# 2_mcu.net
KiCad netlist of a schematic drawn in Altium Designer
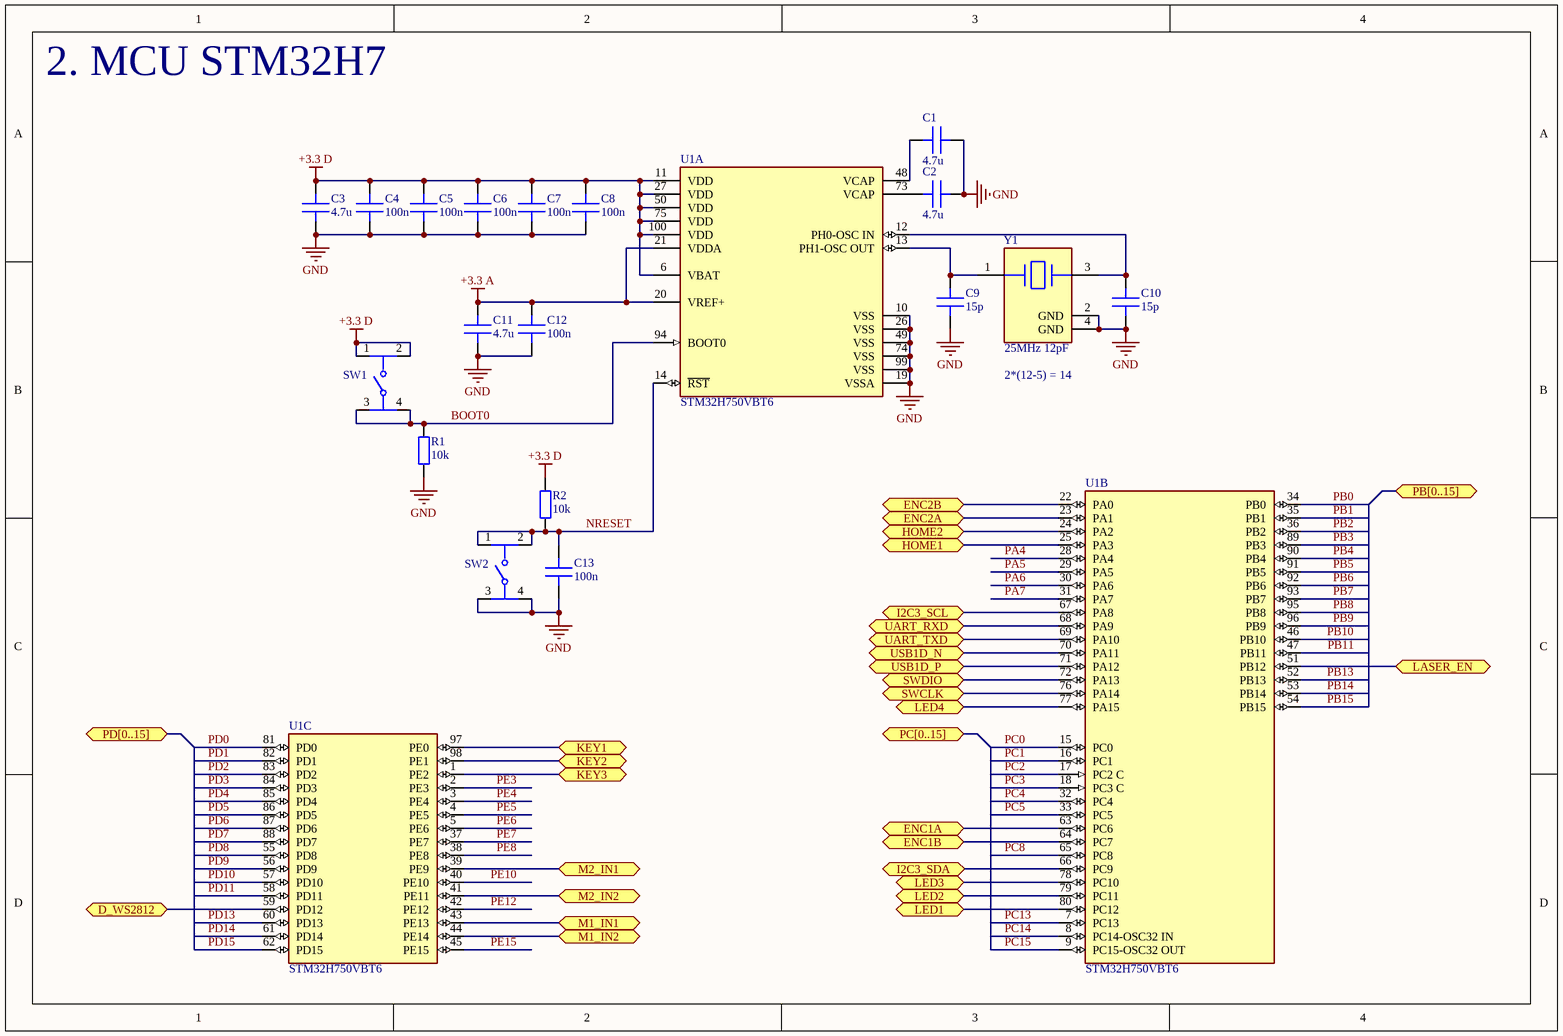
[diagram p0: 2_mcu.SchDoc]

(export (version "E")
  (design (tool "Eeschema 10.0.6"))
  (components
    (comp (ref "C1")
      (value "4.7u")
      (footprint "IPC C C0603 NO SILK")
      (libsource (lib "JLCPCB Library") (part "Generic CAP 0603"))
    )
    (comp (ref "C2")
      (value "4.7u")
      (footprint "IPC C C0603 NO SILK")
      (libsource (lib "JLCPCB Library") (part "Generic CAP 0603"))
    )
    (comp (ref "C3")
      (value "4.7u")
      (footprint "IPC C C0603 NO SILK")
      (libsource (lib "JLCPCB Library") (part "Generic CAP 0603"))
    )
    (comp (ref "C4")
      (value "100n")
      (footprint "IPC C C0402 NO SILK")
      (libsource (lib "JLCPCB Library") (part "Generic CAP 0402"))
    )
    (comp (ref "C5")
      (value "100n")
      (footprint "IPC C C0402 NO SILK")
      (libsource (lib "JLCPCB Library") (part "Generic CAP 0402"))
    )
    (comp (ref "C6")
      (value "100n")
      (footprint "IPC C C0402 NO SILK")
      (libsource (lib "JLCPCB Library") (part "Generic CAP 0402"))
    )
    (comp (ref "C7")
      (value "100n")
      (footprint "IPC C C0402 NO SILK")
      (libsource (lib "JLCPCB Library") (part "Generic CAP 0402"))
    )
    (comp (ref "C8")
      (value "100n")
      (footprint "IPC C C0402 NO SILK")
      (libsource (lib "JLCPCB Library") (part "Generic CAP 0402"))
    )
    (comp (ref "C9")
      (value "15p")
      (footprint "IPC C C0402 NO SILK")
      (libsource (lib "JLCPCB Library") (part "Generic CAP 0402"))
    )
    (comp (ref "C10")
      (value "15p")
      (footprint "IPC C C0402 NO SILK")
      (libsource (lib "JLCPCB Library") (part "Generic CAP 0402"))
    )
    (comp (ref "C11")
      (value "4.7u")
      (footprint "IPC C C0603 NO SILK")
      (libsource (lib "JLCPCB Library") (part "Generic CAP 0603"))
    )
    (comp (ref "C12")
      (value "100n")
      (footprint "IPC C C0402 NO SILK")
      (libsource (lib "JLCPCB Library") (part "Generic CAP 0402"))
    )
    (comp (ref "C13")
      (value "100n")
      (footprint "IPC C C0402 NO SILK")
      (libsource (lib "JLCPCB Library") (part "Generic CAP 0402"))
    )
    (comp (ref "R1")
      (value "10k")
      (footprint "IPC C R0402 NO SILK")
      (libsource (lib "JLCPCB Library") (part "Generic RES 0402"))
    )
    (comp (ref "R2")
      (value "10k")
      (footprint "IPC C R0402 NO SILK")
      (libsource (lib "JLCPCB Library") (part "Generic RES 0402"))
    )
    (comp (ref "SW1")
      (value "PTS810SJM250SMTRLFS")
      (footprint "FP-PTS810SJM250SMTRLFS-MFG")
      (description "SWITCH TACTILE SPST-NO 0.05A 16V")
      (libsource (lib "Altium Content Vault") (part "1adf0dd01260c80cf25a44bfd6b99ba"))
    )
    (comp (ref "SW2")
      (value "PTS810SJM250SMTRLFS")
      (footprint "FP-PTS810SJM250SMTRLFS-MFG")
      (description "SWITCH TACTILE SPST-NO 0.05A 16V")
      (libsource (lib "Altium Content Vault") (part "1adf0dd01260c80cf25a44bfd6b99ba"))
    )
    (comp (ref "U1")
      (value "STM32H750VBT6")
      (footprint "FP-LQFP100-1L-MFG")
      (description "IC MCU 32BIT 128KB FLASH 100LQFP")
      (fields
        (field (name "OCTOPART") "https://octopart.com/stm32h750vbt6-stmicroelectronics-94048547")
        (field (name "MANUFACTURER") "STMicroelectronics")
      )
      (libsource (lib "Altium Content Vault") (part "aca449acb2b80670ba40d015d68dc7a"))
    )
    (comp (ref "Y1")
      (value "ABM8G-25.000MHZ-B4Y-T")
      (footprint "FP-ABM8G-MFG")
      (description "Crystal 25MHz ±30ppm (Tol) ±30ppm (Stability) 10pF FUND 60Ω 4-Pin SMD T/R")
      (fields (field (name "TOLERANCE") "30ppm"))
      (libsource (lib "Altium Content Vault") (part "48e526d86b7f2615d98721063c72f49"))
    )
  )
  (nets
    (net (code "9") (name "+3.3 A") (class "Default")
      (node (ref "C11") (pin "2") (pinfunction "2_2") (pintype "passive"))
      (node (ref "C12") (pin "2") (pinfunction "2_2") (pintype "passive"))
      (node (ref "U1") (pin "20") (pinfunction "VREF+_20") (pintype "power_in"))
      (node (ref "U1") (pin "21") (pinfunction "VDDA_21") (pintype "power_in"))
    )
    (net (code "10") (name "+3.3 D") (class "Default")
      (node (ref "C3") (pin "2") (pinfunction "2_2") (pintype "passive"))
      (node (ref "C4") (pin "2") (pinfunction "2_2") (pintype "passive"))
      (node (ref "C5") (pin "2") (pinfunction "2_2") (pintype "passive"))
      (node (ref "C6") (pin "2") (pinfunction "2_2") (pintype "passive"))
      (node (ref "C7") (pin "2") (pinfunction "2_2") (pintype "passive"))
      (node (ref "C8") (pin "2") (pinfunction "2_2") (pintype "passive"))
      (node (ref "R2") (pin "1") (pinfunction "1_1") (pintype "passive"))
      (node (ref "SW1") (pin "1") (pinfunction "1_1") (pintype "passive"))
      (node (ref "SW1") (pin "2") (pinfunction "2_2") (pintype "passive"))
      (node (ref "U1") (pin "100") (pinfunction "VDD_100") (pintype "power_in"))
      (node (ref "U1") (pin "11") (pinfunction "VDD_11") (pintype "power_in"))
      (node (ref "U1") (pin "27") (pinfunction "VDD_27") (pintype "power_in"))
      (node (ref "U1") (pin "50") (pinfunction "VDD_50") (pintype "power_in"))
      (node (ref "U1") (pin "6") (pinfunction "VBAT_6") (pintype "power_in"))
      (node (ref "U1") (pin "75") (pinfunction "VDD_75") (pintype "power_in"))
    )
    (net (code "11") (name "/BOOT0") (class "Default")
      (node (ref "R1") (pin "1") (pinfunction "1_1") (pintype "passive"))
      (node (ref "SW1") (pin "3") (pinfunction "3_3") (pintype "passive"))
      (node (ref "SW1") (pin "4") (pinfunction "4_4") (pintype "passive"))
      (node (ref "U1") (pin "94") (pinfunction "BOOT0_94") (pintype "input"))
    )
    (net (code "12") (name "/D_WS2812") (class "Default")
      (node (ref "U1") (pin "59") (pinfunction "PD12_59") (pintype "bidirectional"))
    )
    (net (code "13") (name "/ENC1A") (class "Default")
      (node (ref "U1") (pin "63") (pinfunction "PC6_63") (pintype "bidirectional"))
    )
    (net (code "14") (name "/ENC1B") (class "Default")
      (node (ref "U1") (pin "64") (pinfunction "PC7_64") (pintype "bidirectional"))
    )
    (net (code "15") (name "/ENC2A") (class "Default")
      (node (ref "U1") (pin "23") (pinfunction "PA1_23") (pintype "bidirectional"))
    )
    (net (code "16") (name "/ENC2B") (class "Default")
      (node (ref "U1") (pin "22") (pinfunction "PA0_22") (pintype "bidirectional"))
    )
    (net (code "17") (name "/HOME1") (class "Default")
      (node (ref "U1") (pin "25") (pinfunction "PA3_25") (pintype "bidirectional"))
    )
    (net (code "18") (name "/HOME2") (class "Default")
      (node (ref "U1") (pin "24") (pinfunction "PA2_24") (pintype "bidirectional"))
    )
    (net (code "19") (name "/I2C3_SCL") (class "Default")
      (node (ref "U1") (pin "67") (pinfunction "PA8_67") (pintype "bidirectional"))
    )
    (net (code "20") (name "/I2C3_SDA") (class "Default")
      (node (ref "U1") (pin "66") (pinfunction "PC9_66") (pintype "bidirectional"))
    )
    (net (code "21") (name "/KEY1") (class "Default")
      (node (ref "U1") (pin "97") (pinfunction "PE0_97") (pintype "bidirectional"))
    )
    (net (code "22") (name "/KEY2") (class "Default")
      (node (ref "U1") (pin "98") (pinfunction "PE1_98") (pintype "bidirectional"))
    )
    (net (code "23") (name "/KEY3") (class "Default")
      (node (ref "U1") (pin "1") (pinfunction "PE2_1") (pintype "bidirectional"))
    )
    (net (code "24") (name "/LASER_EN") (class "Default")
      (node (ref "U1") (pin "51") (pinfunction "PB12_51") (pintype "bidirectional"))
    )
    (net (code "25") (name "/LED1") (class "Default")
      (node (ref "U1") (pin "80") (pinfunction "PC12_80") (pintype "bidirectional"))
    )
    (net (code "26") (name "/LED2") (class "Default")
      (node (ref "U1") (pin "79") (pinfunction "PC11_79") (pintype "bidirectional"))
    )
    (net (code "27") (name "/LED3") (class "Default")
      (node (ref "U1") (pin "78") (pinfunction "PC10_78") (pintype "bidirectional"))
    )
    (net (code "28") (name "/LED4") (class "Default")
      (node (ref "U1") (pin "77") (pinfunction "PA15_77") (pintype "bidirectional"))
    )
    (net (code "29") (name "/M1_IN1") (class "Default")
      (node (ref "U1") (pin "43") (pinfunction "PE13_43") (pintype "bidirectional"))
    )
    (net (code "30") (name "/M1_IN2") (class "Default")
      (node (ref "U1") (pin "44") (pinfunction "PE14_44") (pintype "bidirectional"))
    )
    (net (code "31") (name "/M2_IN1") (class "Default")
      (node (ref "U1") (pin "39") (pinfunction "PE9_39") (pintype "bidirectional"))
    )
    (net (code "32") (name "/M2_IN2") (class "Default")
      (node (ref "U1") (pin "41") (pinfunction "PE11_41") (pintype "bidirectional"))
    )
    (net (code "33") (name "/NRESET") (class "Default")
      (node (ref "C13") (pin "2") (pinfunction "2_2") (pintype "passive"))
      (node (ref "R2") (pin "2") (pinfunction "2_2") (pintype "passive"))
      (node (ref "SW2") (pin "1") (pinfunction "1_1") (pintype "passive"))
      (node (ref "SW2") (pin "2") (pinfunction "2_2") (pintype "passive"))
      (node (ref "U1") (pin "14") (pinfunction "~{RST}_14") (pintype "bidirectional"))
    )
    (net (code "34") (name "/PA4") (class "Default")
      (node (ref "U1") (pin "28") (pinfunction "PA4_28") (pintype "bidirectional"))
    )
    (net (code "35") (name "/PA5") (class "Default")
      (node (ref "U1") (pin "29") (pinfunction "PA5_29") (pintype "bidirectional"))
    )
    (net (code "36") (name "/PA6") (class "Default")
      (node (ref "U1") (pin "30") (pinfunction "PA6_30") (pintype "bidirectional"))
    )
    (net (code "37") (name "/PA7") (class "Default")
      (node (ref "U1") (pin "31") (pinfunction "PA7_31") (pintype "bidirectional"))
    )
    (net (code "38") (name "/PB0") (class "Default")
      (node (ref "U1") (pin "34") (pinfunction "PB0_34") (pintype "bidirectional"))
    )
    (net (code "39") (name "/PB1") (class "Default")
      (node (ref "U1") (pin "35") (pinfunction "PB1_35") (pintype "bidirectional"))
    )
    (net (code "40") (name "/PB2") (class "Default")
      (node (ref "U1") (pin "36") (pinfunction "PB2_36") (pintype "bidirectional"))
    )
    (net (code "41") (name "/PB3") (class "Default")
      (node (ref "U1") (pin "89") (pinfunction "PB3_89") (pintype "bidirectional"))
    )
    (net (code "42") (name "/PB4") (class "Default")
      (node (ref "U1") (pin "90") (pinfunction "PB4_90") (pintype "bidirectional"))
    )
    (net (code "43") (name "/PB5") (class "Default")
      (node (ref "U1") (pin "91") (pinfunction "PB5_91") (pintype "bidirectional"))
    )
    (net (code "44") (name "/PB6") (class "Default")
      (node (ref "U1") (pin "92") (pinfunction "PB6_92") (pintype "bidirectional"))
    )
    (net (code "45") (name "/PB7") (class "Default")
      (node (ref "U1") (pin "93") (pinfunction "PB7_93") (pintype "bidirectional"))
    )
    (net (code "46") (name "/PB8") (class "Default")
      (node (ref "U1") (pin "95") (pinfunction "PB8_95") (pintype "bidirectional"))
    )
    (net (code "47") (name "/PB9") (class "Default")
      (node (ref "U1") (pin "96") (pinfunction "PB9_96") (pintype "bidirectional"))
    )
    (net (code "48") (name "/PB10") (class "Default")
      (node (ref "U1") (pin "46") (pinfunction "PB10_46") (pintype "bidirectional"))
    )
    (net (code "49") (name "/PB11") (class "Default")
      (node (ref "U1") (pin "47") (pinfunction "PB11_47") (pintype "bidirectional"))
    )
    (net (code "50") (name "/PB13") (class "Default")
      (node (ref "U1") (pin "52") (pinfunction "PB13_52") (pintype "bidirectional"))
    )
    (net (code "51") (name "/PB14") (class "Default")
      (node (ref "U1") (pin "53") (pinfunction "PB14_53") (pintype "bidirectional"))
    )
    (net (code "52") (name "/PB15") (class "Default")
      (node (ref "U1") (pin "54") (pinfunction "PB15_54") (pintype "bidirectional"))
    )
    (net (code "54") (name "/PC0") (class "Default")
      (node (ref "U1") (pin "15") (pinfunction "PC0_15") (pintype "bidirectional"))
    )
    (net (code "55") (name "/PC1") (class "Default")
      (node (ref "U1") (pin "16") (pinfunction "PC1_16") (pintype "bidirectional"))
    )
    (net (code "56") (name "/PC2") (class "Default")
      (node (ref "U1") (pin "17") (pinfunction "PC2_C_17") (pintype "input"))
    )
    (net (code "57") (name "/PC3") (class "Default")
      (node (ref "U1") (pin "18") (pinfunction "PC3_C_18") (pintype "input"))
    )
    (net (code "58") (name "/PC4") (class "Default")
      (node (ref "U1") (pin "32") (pinfunction "PC4_32") (pintype "bidirectional"))
    )
    (net (code "59") (name "/PC5") (class "Default")
      (node (ref "U1") (pin "33") (pinfunction "PC5_33") (pintype "bidirectional"))
    )
    (net (code "60") (name "/PC8") (class "Default")
      (node (ref "U1") (pin "65") (pinfunction "PC8_65") (pintype "bidirectional"))
    )
    (net (code "61") (name "/PC13") (class "Default")
      (node (ref "U1") (pin "7") (pinfunction "PC13_7") (pintype "bidirectional"))
    )
    (net (code "62") (name "/PC14") (class "Default")
      (node (ref "U1") (pin "8") (pinfunction "PC14-OSC32_IN_8") (pintype "bidirectional"))
    )
    (net (code "63") (name "/PC15") (class "Default")
      (node (ref "U1") (pin "9") (pinfunction "PC15-OSC32_OUT_9") (pintype "bidirectional"))
    )
    (net (code "65") (name "/PD0") (class "Default")
      (node (ref "U1") (pin "81") (pinfunction "PD0_81") (pintype "bidirectional"))
    )
    (net (code "66") (name "/PD1") (class "Default")
      (node (ref "U1") (pin "82") (pinfunction "PD1_82") (pintype "bidirectional"))
    )
    (net (code "67") (name "/PD2") (class "Default")
      (node (ref "U1") (pin "83") (pinfunction "PD2_83") (pintype "bidirectional"))
    )
    (net (code "68") (name "/PD3") (class "Default")
      (node (ref "U1") (pin "84") (pinfunction "PD3_84") (pintype "bidirectional"))
    )
    (net (code "69") (name "/PD4") (class "Default")
      (node (ref "U1") (pin "85") (pinfunction "PD4_85") (pintype "bidirectional"))
    )
    (net (code "70") (name "/PD5") (class "Default")
      (node (ref "U1") (pin "86") (pinfunction "PD5_86") (pintype "bidirectional"))
    )
    (net (code "71") (name "/PD6") (class "Default")
      (node (ref "U1") (pin "87") (pinfunction "PD6_87") (pintype "bidirectional"))
    )
    (net (code "72") (name "/PD7") (class "Default")
      (node (ref "U1") (pin "88") (pinfunction "PD7_88") (pintype "bidirectional"))
    )
    (net (code "73") (name "/PD8") (class "Default")
      (node (ref "U1") (pin "55") (pinfunction "PD8_55") (pintype "bidirectional"))
    )
    (net (code "74") (name "/PD9") (class "Default")
      (node (ref "U1") (pin "56") (pinfunction "PD9_56") (pintype "bidirectional"))
    )
    (net (code "75") (name "/PD10") (class "Default")
      (node (ref "U1") (pin "57") (pinfunction "PD10_57") (pintype "bidirectional"))
    )
    (net (code "76") (name "/PD11") (class "Default")
      (node (ref "U1") (pin "58") (pinfunction "PD11_58") (pintype "bidirectional"))
    )
    (net (code "77") (name "/PD13") (class "Default")
      (node (ref "U1") (pin "60") (pinfunction "PD13_60") (pintype "bidirectional"))
    )
    (net (code "78") (name "/PD14") (class "Default")
      (node (ref "U1") (pin "61") (pinfunction "PD14_61") (pintype "bidirectional"))
    )
    (net (code "79") (name "/PD15") (class "Default")
      (node (ref "U1") (pin "62") (pinfunction "PD15_62") (pintype "bidirectional"))
    )
    (net (code "81") (name "/PE3") (class "Default")
      (node (ref "U1") (pin "2") (pinfunction "PE3_2") (pintype "bidirectional"))
    )
    (net (code "82") (name "/PE4") (class "Default")
      (node (ref "U1") (pin "3") (pinfunction "PE4_3") (pintype "bidirectional"))
    )
    (net (code "83") (name "/PE5") (class "Default")
      (node (ref "U1") (pin "4") (pinfunction "PE5_4") (pintype "bidirectional"))
    )
    (net (code "84") (name "/PE6") (class "Default")
      (node (ref "U1") (pin "5") (pinfunction "PE6_5") (pintype "bidirectional"))
    )
    (net (code "85") (name "/PE7") (class "Default")
      (node (ref "U1") (pin "37") (pinfunction "PE7_37") (pintype "bidirectional"))
    )
    (net (code "86") (name "/PE8") (class "Default")
      (node (ref "U1") (pin "38") (pinfunction "PE8_38") (pintype "bidirectional"))
    )
    (net (code "87") (name "/PE10") (class "Default")
      (node (ref "U1") (pin "40") (pinfunction "PE10_40") (pintype "bidirectional"))
    )
    (net (code "88") (name "/PE12") (class "Default")
      (node (ref "U1") (pin "42") (pinfunction "PE12_42") (pintype "bidirectional"))
    )
    (net (code "89") (name "/PE15") (class "Default")
      (node (ref "U1") (pin "45") (pinfunction "PE15_45") (pintype "bidirectional"))
    )
    (net (code "90") (name "/SWCLK") (class "Default")
      (node (ref "U1") (pin "76") (pinfunction "PA14_76") (pintype "bidirectional"))
    )
    (net (code "91") (name "/SWDIO") (class "Default")
      (node (ref "U1") (pin "72") (pinfunction "PA13_72") (pintype "bidirectional"))
    )
    (net (code "92") (name "/UART_RXD") (class "Default")
      (node (ref "U1") (pin "68") (pinfunction "PA9_68") (pintype "bidirectional"))
    )
    (net (code "93") (name "/UART_TXD") (class "Default")
      (node (ref "U1") (pin "69") (pinfunction "PA10_69") (pintype "bidirectional"))
    )
    (net (code "94") (name "/USB1D_N") (class "Default")
      (node (ref "U1") (pin "70") (pinfunction "PA11_70") (pintype "bidirectional"))
    )
    (net (code "95") (name "/USB1D_P") (class "Default")
      (node (ref "U1") (pin "71") (pinfunction "PA12_71") (pintype "bidirectional"))
    )
    (net (code "96") (name "GND") (class "Default")
      (node (ref "C1") (pin "1") (pinfunction "1_1") (pintype "passive"))
      (node (ref "C10") (pin "1") (pinfunction "1_1") (pintype "passive"))
      (node (ref "C11") (pin "1") (pinfunction "1_1") (pintype "passive"))
      (node (ref "C12") (pin "1") (pinfunction "1_1") (pintype "passive"))
      (node (ref "C13") (pin "1") (pinfunction "1_1") (pintype "passive"))
      (node (ref "C2") (pin "1") (pinfunction "1_1") (pintype "passive"))
      (node (ref "C3") (pin "1") (pinfunction "1_1") (pintype "passive"))
      (node (ref "C4") (pin "1") (pinfunction "1_1") (pintype "passive"))
      (node (ref "C5") (pin "1") (pinfunction "1_1") (pintype "passive"))
      (node (ref "C6") (pin "1") (pinfunction "1_1") (pintype "passive"))
      (node (ref "C7") (pin "1") (pinfunction "1_1") (pintype "passive"))
      (node (ref "C8") (pin "1") (pinfunction "1_1") (pintype "passive"))
      (node (ref "C9") (pin "1") (pinfunction "1_1") (pintype "passive"))
      (node (ref "R1") (pin "2") (pinfunction "2_2") (pintype "passive"))
      (node (ref "SW2") (pin "3") (pinfunction "3_3") (pintype "passive"))
      (node (ref "SW2") (pin "4") (pinfunction "4_4") (pintype "passive"))
      (node (ref "U1") (pin "10") (pinfunction "VSS_10") (pintype "power_in"))
      (node (ref "U1") (pin "19") (pinfunction "VSSA_19") (pintype "power_in"))
      (node (ref "U1") (pin "26") (pinfunction "VSS_26") (pintype "power_in"))
      (node (ref "U1") (pin "49") (pinfunction "VSS_49") (pintype "power_in"))
      (node (ref "U1") (pin "74") (pinfunction "VSS_74") (pintype "power_in"))
      (node (ref "U1") (pin "99") (pinfunction "VSS_99") (pintype "power_in"))
      (node (ref "Y1") (pin "2") (pinfunction "GND_2") (pintype "power_in"))
      (node (ref "Y1") (pin "4") (pinfunction "GND_4") (pintype "power_in"))
    )
    (net (code "97") (name "Net-(C1-Pad2)") (class "Default")
      (node (ref "C1") (pin "2") (pinfunction "2_2") (pintype "passive"))
      (node (ref "U1") (pin "48") (pinfunction "VCAP_48") (pintype "power_in"))
    )
    (net (code "98") (name "Net-(C2-Pad2)") (class "Default")
      (node (ref "C2") (pin "2") (pinfunction "2_2") (pintype "passive"))
      (node (ref "U1") (pin "73") (pinfunction "VCAP_73") (pintype "power_in"))
    )
    (net (code "99") (name "Net-(U1A-PH0-OSC_IN)") (class "Default")
      (node (ref "C10") (pin "2") (pinfunction "2_2") (pintype "passive"))
      (node (ref "U1") (pin "12") (pinfunction "PH0-OSC_IN_12") (pintype "bidirectional"))
      (node (ref "Y1") (pin "3") (pinfunction "3_3") (pintype "passive"))
    )
    (net (code "100") (name "Net-(U1A-PH1-OSC_OUT)") (class "Default")
      (node (ref "C9") (pin "2") (pinfunction "2_2") (pintype "passive"))
      (node (ref "U1") (pin "13") (pinfunction "PH1-OSC_OUT_13") (pintype "bidirectional"))
      (node (ref "Y1") (pin "1") (pinfunction "1_1") (pintype "passive"))
    )
  )
)
